# H3_USB.net
KiCad netlist of a schematic drawn in Altium Designer
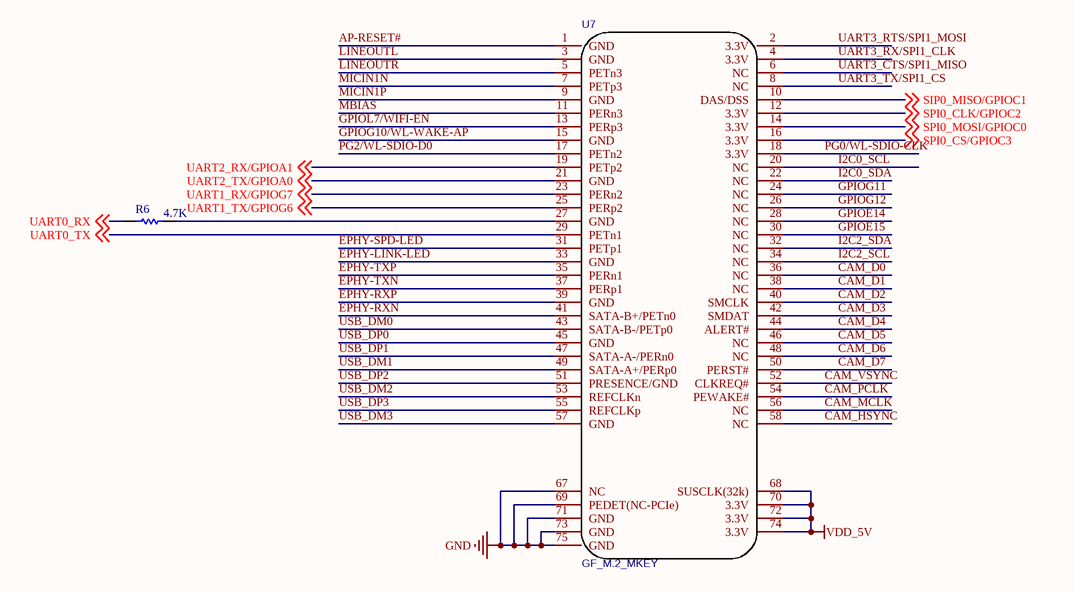
[diagram p0: H3_USB.SchDoc]

(export (version "E")
  (design (tool "Eeschema 10.0.6"))
  (components
    (comp (ref "R6")
      (value "4.7K")
      (footprint "H3_Core:R0402")
      (description "电阻")
      (fields (field (name "PUBLISHER") "Altium Limited"))
      (libsource (lib "Devices") (part "RES0402"))
    )
    (comp (ref "U7")
      (value "GF_M.2_MKEY")
      (footprint "M.2 M-KEY_GF:GF_M.2_M_KEY")
      (fields (field (name "BOM_MANUFACTURER PART") "SHOWNAME=F") (field (name "CONTRIBUTOR") "redgragon"))
      (libsource (lib "M.2 M-KEY底座与金手指") (part "GF_M.2_MKEY"))
    )
  )
  (nets
    (net (code "1") (name "/AP-RESET#") (class "Default")
      (node (ref "U7") (pin "1") (pinfunction "GND_1") (pintype "passive"))
    )
    (net (code "2") (name "/CAM_D0") (class "Default")
      (node (ref "U7") (pin "36") (pinfunction "NC_36") (pintype "passive"))
    )
    (net (code "3") (name "/CAM_D1") (class "Default")
      (node (ref "U7") (pin "38") (pinfunction "NC_38") (pintype "passive"))
    )
    (net (code "4") (name "/CAM_D2") (class "Default")
      (node (ref "U7") (pin "40") (pinfunction "SMCLK_40") (pintype "passive"))
    )
    (net (code "5") (name "/CAM_D3") (class "Default")
      (node (ref "U7") (pin "42") (pinfunction "SMDAT_42") (pintype "passive"))
    )
    (net (code "6") (name "/CAM_D4") (class "Default")
      (node (ref "U7") (pin "44") (pinfunction "ALERT#_44") (pintype "passive"))
    )
    (net (code "7") (name "/CAM_D5") (class "Default")
      (node (ref "U7") (pin "46") (pinfunction "NC_46") (pintype "passive"))
    )
    (net (code "8") (name "/CAM_D6") (class "Default")
      (node (ref "U7") (pin "48") (pinfunction "NC_48") (pintype "passive"))
    )
    (net (code "9") (name "/CAM_D7") (class "Default")
      (node (ref "U7") (pin "50") (pinfunction "PERST#_50") (pintype "passive"))
    )
    (net (code "10") (name "/CAM_HSYNC") (class "Default")
      (node (ref "U7") (pin "58") (pinfunction "NC_58") (pintype "passive"))
    )
    (net (code "11") (name "/CAM_MCLK") (class "Default")
      (node (ref "U7") (pin "56") (pinfunction "NC_56") (pintype "passive"))
    )
    (net (code "12") (name "/CAM_PCLK") (class "Default")
      (node (ref "U7") (pin "54") (pinfunction "PEWAKE#_54") (pintype "passive"))
    )
    (net (code "13") (name "/CAM_VSYNC") (class "Default")
      (node (ref "U7") (pin "52") (pinfunction "CLKREQ#_52") (pintype "passive"))
    )
    (net (code "14") (name "/EPHY-LINK-LED") (class "Default")
      (node (ref "U7") (pin "33") (pinfunction "GND_33") (pintype "passive"))
    )
    (net (code "15") (name "/EPHY-RXN") (class "Default")
      (node (ref "U7") (pin "41") (pinfunction "SATA-B+/PETn0_41") (pintype "passive"))
    )
    (net (code "16") (name "/EPHY-RXP") (class "Default")
      (node (ref "U7") (pin "39") (pinfunction "GND_39") (pintype "passive"))
    )
    (net (code "17") (name "/EPHY-SPD-LED") (class "Default")
      (node (ref "U7") (pin "31") (pinfunction "PETp1_31") (pintype "passive"))
    )
    (net (code "18") (name "/EPHY-TXN") (class "Default")
      (node (ref "U7") (pin "37") (pinfunction "PERp1_37") (pintype "passive"))
    )
    (net (code "19") (name "/EPHY-TXP") (class "Default")
      (node (ref "U7") (pin "35") (pinfunction "PERn1_35") (pintype "passive"))
    )
    (net (code "20") (name "/GPIOE14") (class "Default")
      (node (ref "U7") (pin "28") (pinfunction "NC_28") (pintype "passive"))
    )
    (net (code "21") (name "/GPIOE15") (class "Default")
      (node (ref "U7") (pin "30") (pinfunction "NC_30") (pintype "passive"))
    )
    (net (code "22") (name "/GPIOG10{slash}WL-WAKE-AP") (class "Default")
      (node (ref "U7") (pin "15") (pinfunction "GND_15") (pintype "passive"))
    )
    (net (code "23") (name "/GPIOG11") (class "Default")
      (node (ref "U7") (pin "24") (pinfunction "NC_24") (pintype "passive"))
    )
    (net (code "24") (name "/GPIOG12") (class "Default")
      (node (ref "U7") (pin "26") (pinfunction "NC_26") (pintype "passive"))
    )
    (net (code "25") (name "/GPIOL7{slash}WIFI-EN") (class "Default")
      (node (ref "U7") (pin "13") (pinfunction "PERp3_13") (pintype "passive"))
    )
    (net (code "26") (name "/I2C0_SCL") (class "Default")
      (node (ref "U7") (pin "20") (pinfunction "NC_20") (pintype "passive"))
    )
    (net (code "27") (name "/I2C0_SDA") (class "Default")
      (node (ref "U7") (pin "22") (pinfunction "NC_22") (pintype "passive"))
    )
    (net (code "28") (name "/I2C2_SCL") (class "Default")
      (node (ref "U7") (pin "34") (pinfunction "NC_34") (pintype "passive"))
    )
    (net (code "29") (name "/I2C2_SDA") (class "Default")
      (node (ref "U7") (pin "32") (pinfunction "NC_32") (pintype "passive"))
    )
    (net (code "30") (name "/LINEOUTL") (class "Default")
      (node (ref "U7") (pin "3") (pinfunction "GND_3") (pintype "passive"))
    )
    (net (code "31") (name "/LINEOUTR") (class "Default")
      (node (ref "U7") (pin "5") (pinfunction "PETn3_5") (pintype "passive"))
    )
    (net (code "32") (name "/MBIAS") (class "Default")
      (node (ref "U7") (pin "11") (pinfunction "PERn3_11") (pintype "passive"))
    )
    (net (code "33") (name "/MICIN1N") (class "Default")
      (node (ref "U7") (pin "7") (pinfunction "PETp3_7") (pintype "passive"))
    )
    (net (code "34") (name "/MICIN1P") (class "Default")
      (node (ref "U7") (pin "9") (pinfunction "GND_9") (pintype "passive"))
    )
    (net (code "35") (name "/PG0{slash}WL-SDIO-CLK") (class "Default")
      (node (ref "U7") (pin "18") (pinfunction "3.3V_18") (pintype "passive"))
    )
    (net (code "36") (name "/PG2{slash}WL-SDIO-D0") (class "Default")
      (node (ref "U7") (pin "17") (pinfunction "PETn2_17") (pintype "passive"))
    )
    (net (code "37") (name "/UART3_CTS{slash}SPI1_MISO") (class "Default")
      (node (ref "U7") (pin "6") (pinfunction "NC_6") (pintype "passive"))
    )
    (net (code "38") (name "/UART3_RTS{slash}SPI1_MOSI") (class "Default")
      (node (ref "U7") (pin "2") (pinfunction "3.3V_2") (pintype "passive"))
    )
    (net (code "39") (name "/UART3_RX{slash}SPI1_CLK") (class "Default")
      (node (ref "U7") (pin "4") (pinfunction "3.3V_4") (pintype "passive"))
    )
    (net (code "40") (name "/UART3_TX{slash}SPI1_CS") (class "Default")
      (node (ref "U7") (pin "8") (pinfunction "NC_8") (pintype "passive"))
    )
    (net (code "41") (name "/USB_DM0") (class "Default")
      (node (ref "U7") (pin "43") (pinfunction "SATA-B-/PETp0_43") (pintype "passive"))
    )
    (net (code "42") (name "/USB_DM1") (class "Default")
      (node (ref "U7") (pin "49") (pinfunction "SATA-A+/PERp0_49") (pintype "passive"))
    )
    (net (code "43") (name "/USB_DM2") (class "Default")
      (node (ref "U7") (pin "53") (pinfunction "REFCLKn_53") (pintype "passive"))
    )
    (net (code "44") (name "/USB_DM3") (class "Default")
      (node (ref "U7") (pin "57") (pinfunction "GND_57") (pintype "passive"))
    )
    (net (code "45") (name "/USB_DP0") (class "Default")
      (node (ref "U7") (pin "45") (pinfunction "GND_45") (pintype "passive"))
    )
    (net (code "46") (name "/USB_DP1") (class "Default")
      (node (ref "U7") (pin "47") (pinfunction "SATA-A-/PERn0_47") (pintype "passive"))
    )
    (net (code "47") (name "/USB_DP2") (class "Default")
      (node (ref "U7") (pin "51") (pinfunction "PRESENCE/GND_51") (pintype "passive"))
    )
    (net (code "48") (name "/USB_DP3") (class "Default")
      (node (ref "U7") (pin "55") (pinfunction "REFCLKp_55") (pintype "passive"))
    )
    (net (code "49") (name "GND") (class "Default")
      (node (ref "U7") (pin "67") (pinfunction "NC_67") (pintype "passive"))
      (node (ref "U7") (pin "69") (pinfunction "PEDET(NC-PCIe)_69") (pintype "passive"))
      (node (ref "U7") (pin "71") (pinfunction "GND_71") (pintype "passive"))
      (node (ref "U7") (pin "73") (pinfunction "GND_73") (pintype "passive"))
      (node (ref "U7") (pin "75") (pinfunction "GND_75") (pintype "passive"))
    )
    (net (code "50") (name "Net-(R6-Pad1)") (class "Default")
      (node (ref "R6") (pin "1") (pinfunction "1_1") (pintype "passive"))
      (node (ref "U7") (pin "27") (pinfunction "GND_27") (pintype "passive"))
    )
    (net (code "51") (name "SIP0_MISO{slash}GPIOC1") (class "Default")
      (node (ref "U7") (pin "10") (pinfunction "DAS/DSS_10") (pintype "passive"))
    )
    (net (code "52") (name "SPI0_CLK{slash}GPIOC2") (class "Default")
      (node (ref "U7") (pin "12") (pinfunction "3.3V_12") (pintype "passive"))
    )
    (net (code "53") (name "SPI0_CS{slash}GPIOC3") (class "Default")
      (node (ref "U7") (pin "16") (pinfunction "3.3V_16") (pintype "passive"))
    )
    (net (code "54") (name "SPI0_MOSI{slash}GPIOC0") (class "Default")
      (node (ref "U7") (pin "14") (pinfunction "3.3V_14") (pintype "passive"))
    )
    (net (code "55") (name "UART0_RX") (class "Default")
      (node (ref "R6") (pin "2") (pinfunction "2_2") (pintype "passive"))
    )
    (net (code "56") (name "UART0_TX") (class "Default")
      (node (ref "U7") (pin "29") (pinfunction "PETn1_29") (pintype "passive"))
    )
    (net (code "57") (name "UART1_RX{slash}GPIOG7") (class "Default")
      (node (ref "U7") (pin "23") (pinfunction "PERn2_23") (pintype "passive"))
    )
    (net (code "58") (name "UART1_TX{slash}GPIOG6") (class "Default")
      (node (ref "U7") (pin "25") (pinfunction "PERp2_25") (pintype "passive"))
    )
    (net (code "59") (name "UART2_RX{slash}GPIOA1") (class "Default")
      (node (ref "U7") (pin "19") (pinfunction "PETp2_19") (pintype "passive"))
    )
    (net (code "60") (name "UART2_TX{slash}GPIOA0") (class "Default")
      (node (ref "U7") (pin "21") (pinfunction "GND_21") (pintype "passive"))
    )
    (net (code "61") (name "VDD_5V") (class "Default")
      (node (ref "U7") (pin "68") (pinfunction "SUSCLK(32k)_68") (pintype "passive"))
      (node (ref "U7") (pin "70") (pinfunction "3.3V_70") (pintype "passive"))
      (node (ref "U7") (pin "72") (pinfunction "3.3V_72") (pintype "passive"))
      (node (ref "U7") (pin "74") (pinfunction "3.3V_74") (pintype "passive"))
    )
  )
)
